# power.net
KiCad netlist of a schematic drawn in Altium Designer
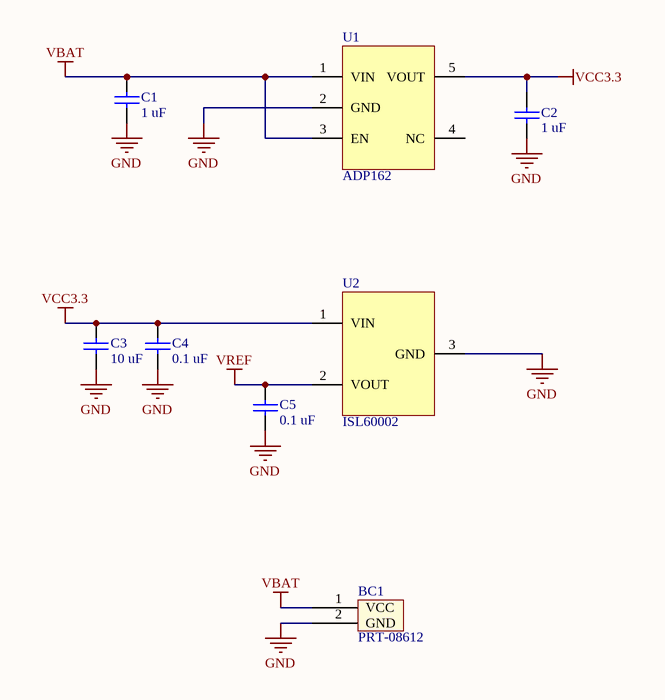
[diagram p0: power.SchDoc]

(export (version "E")
  (design (tool "Eeschema 10.0.6"))
  (components
    (comp (ref "BC1")
      (value "PRT-08612")
      (footprint "JST PH 2PIN")
      (description "2-pin JST-PH 2mm Battery Connector")
      (libsource (lib "opo_general") (part "JST-PH-2mm-2Pin"))
    )
    (comp (ref "C1")
      (value "1 uF")
      (footprint "0402")
      (description "Ceramic capacitor, 1 uF, 0402 package")
      (fields (field (name "TOLERANCE") "10%") (field (name "Comment") "Ceramic capacitor"))
      (libsource (lib "rlc") (part "C_1u_0402_ceramic"))
    )
    (comp (ref "C2")
      (value "1 uF")
      (footprint "0402")
      (description "Ceramic capacitor, 1 uF, 0402 package")
      (fields (field (name "TOLERANCE") "10%") (field (name "Comment") "Ceramic capacitor"))
      (libsource (lib "rlc") (part "C_1u_0402_ceramic"))
    )
    (comp (ref "C3")
      (value "10 uF")
      (footprint "0402")
      (description "Ceramic capacitor, 10 uF, 0402 package")
      (fields (field (name "TOLERANCE") "20%") (field (name "Comment") "Ceramic capacitor"))
      (libsource (lib "rlc") (part "C_10u_0402_ceramic"))
    )
    (comp (ref "C4")
      (value "0.1 uF")
      (footprint "0402")
      (description "Ceramic capacitor, 0.1u, 0402 package")
      (fields (field (name "TOLERANCE") "10%") (field (name "Comment") "Ceramic capacitor"))
      (libsource (lib "rlc") (part "C_0.1u_0402_ceramic"))
    )
    (comp (ref "C5")
      (value "0.1 uF")
      (footprint "0402")
      (description "Ceramic capacitor, 0.1u, 0402 package")
      (fields (field (name "TOLERANCE") "10%") (field (name "Comment") "Ceramic capacitor"))
      (libsource (lib "rlc") (part "C_0.1u_0402_ceramic"))
    )
    (comp (ref "U1")
      (value "ADP162")
      (footprint "TSOT23-5")
      (description "IC REG LDO 3.3V 0.15A TSOT23-5")
      (libsource (lib "opo_general") (part "ADP162"))
    )
    (comp (ref "U2")
      (value "ISL60002")
      (footprint "SOT23-3N")
      (description "IC VREF SERIES PREC SOT-23-3")
      (libsource (lib "opo_general") (part "ISL60002"))
    )
  )
  (nets
    (net (code "1") (name "GND") (class "Default")
      (node (ref "BC1") (pin "2") (pinfunction "GND_2") (pintype "passive"))
      (node (ref "C1") (pin "2") (pintype "passive"))
      (node (ref "C2") (pin "2") (pintype "passive"))
      (node (ref "C3") (pin "2") (pintype "passive"))
      (node (ref "C4") (pin "2") (pintype "passive"))
      (node (ref "C5") (pin "2") (pintype "passive"))
      (node (ref "U1") (pin "2") (pinfunction "GND_2") (pintype "passive"))
      (node (ref "U2") (pin "3") (pinfunction "GND_3") (pintype "passive"))
    )
    (net (code "2") (name "VBAT") (class "Default")
      (node (ref "BC1") (pin "1") (pinfunction "VCC_1") (pintype "passive"))
      (node (ref "C1") (pin "1") (pintype "passive"))
      (node (ref "U1") (pin "1") (pinfunction "VIN_1") (pintype "passive"))
      (node (ref "U1") (pin "3") (pinfunction "EN_3") (pintype "passive"))
    )
    (net (code "3") (name "VCC3.3") (class "Default")
      (node (ref "C2") (pin "1") (pintype "passive"))
      (node (ref "C3") (pin "1") (pintype "passive"))
      (node (ref "C4") (pin "1") (pintype "passive"))
      (node (ref "U1") (pin "5") (pinfunction "VOUT_5") (pintype "passive"))
      (node (ref "U2") (pin "1") (pinfunction "VIN_1") (pintype "passive"))
    )
    (net (code "4") (name "VREF") (class "Default")
      (node (ref "C5") (pin "1") (pintype "passive"))
      (node (ref "U2") (pin "2") (pinfunction "VOUT_2") (pintype "passive"))
    )
    (net (code "5") (name "unconnected-(BC1-Pad3)") (class "Default")
      (node (ref "BC1") (pin "3") (pinfunction "3_3") (pintype "passive"))
    )
    (net (code "6") (name "unconnected-(BC1-Pad4)") (class "Default")
      (node (ref "BC1") (pin "4") (pinfunction "4_4") (pintype "passive"))
    )
    (net (code "7") (name "unconnected-(U1-NC-Pad4)") (class "Default")
      (node (ref "U1") (pin "4") (pinfunction "NC_4") (pintype "passive"))
    )
  )
)
